# OpenPack_BATMOD_V2p0_MAN.net
KiCad netlist of a schematic drawn in Altium Designer
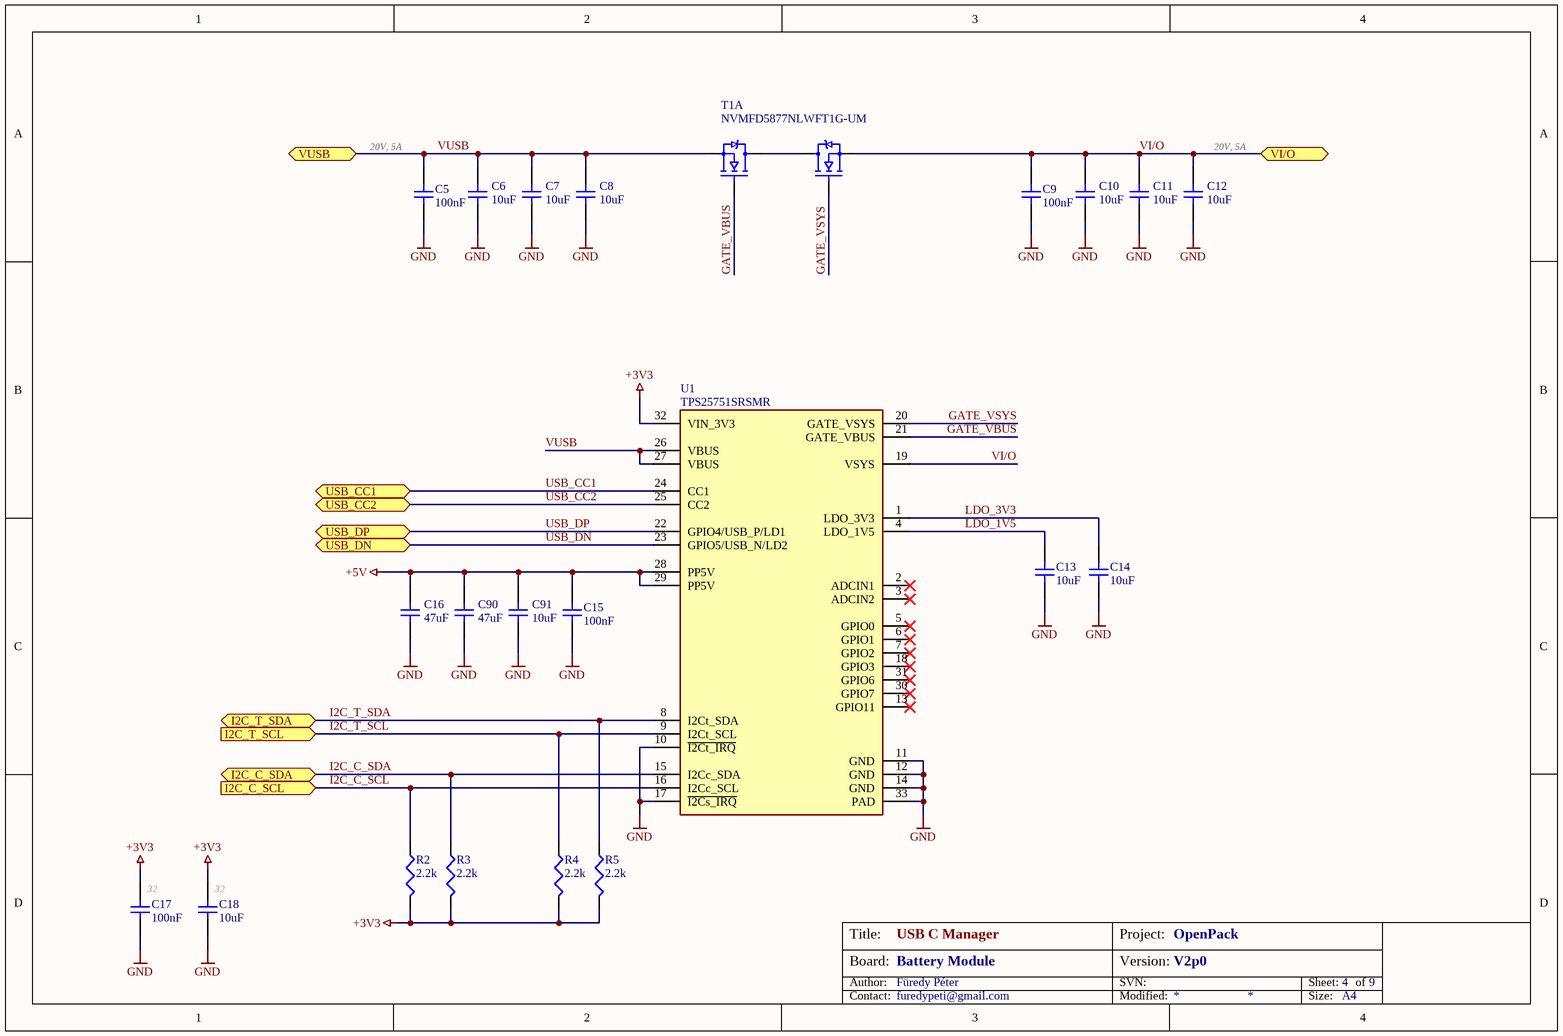
[diagram p0: OpenPack_BATMOD_V2p0_MAN.SchDoc]

(export (version "E")
  (design (tool "Eeschema 10.0.6"))
  (components
    (comp (ref "C5")
      (value "100nF")
      (footprint "CAP_0603")
      (description "MLCC capacitor")
      (libsource (lib "SCHLIB") (part "NP-CAPACITOR"))
    )
    (comp (ref "C6")
      (value "10uF")
      (footprint "CAP_1210")
      (description "UMK325BJ106KM-P")
      (fields (field (name "PART NUMBER") "810-CGA6P1X7R1N106K2"))
      (libsource (lib "SCHLIB") (part "NP-CAPACITOR"))
    )
    (comp (ref "C7")
      (value "10uF")
      (footprint "CAP_1210")
      (description "UMK325BJ106KM-P")
      (fields (field (name "PART NUMBER") "810-CGA6P1X7R1N106K2"))
      (libsource (lib "SCHLIB") (part "NP-CAPACITOR"))
    )
    (comp (ref "C8")
      (value "10uF")
      (footprint "CAP_1210")
      (description "UMK325BJ106KM-P")
      (fields (field (name "PART NUMBER") "810-CGA6P1X7R1N106K2"))
      (libsource (lib "SCHLIB") (part "NP-CAPACITOR"))
    )
    (comp (ref "C9")
      (value "100nF")
      (footprint "CAP_0603")
      (description "MLCC capacitor")
      (libsource (lib "SCHLIB") (part "NP-CAPACITOR"))
    )
    (comp (ref "C10")
      (value "10uF")
      (footprint "CAP_1210")
      (description "UMK325BJ106KM-P")
      (fields (field (name "PART NUMBER") "810-CGA6P1X7R1N106K2"))
      (libsource (lib "SCHLIB") (part "NP-CAPACITOR"))
    )
    (comp (ref "C11")
      (value "10uF")
      (footprint "CAP_1210")
      (description "UMK325BJ106KM-P")
      (fields (field (name "PART NUMBER") "810-CGA6P1X7R1N106K2"))
      (libsource (lib "SCHLIB") (part "NP-CAPACITOR"))
    )
    (comp (ref "C12")
      (value "10uF")
      (footprint "CAP_1210")
      (description "UMK325BJ106KM-P")
      (fields (field (name "PART NUMBER") "810-CGA6P1X7R1N106K2"))
      (libsource (lib "SCHLIB") (part "NP-CAPACITOR"))
    )
    (comp (ref "C13")
      (value "10uF")
      (footprint "CAP_0603")
      (description "MLCC capacitor")
      (libsource (lib "SCHLIB") (part "NP-CAPACITOR"))
    )
    (comp (ref "C14")
      (value "10uF")
      (footprint "CAP_0603")
      (description "MLCC capacitor")
      (libsource (lib "SCHLIB") (part "NP-CAPACITOR"))
    )
    (comp (ref "C15")
      (value "100nF")
      (footprint "CAP_0603")
      (description "MLCC capacitor")
      (libsource (lib "SCHLIB") (part "NP-CAPACITOR"))
    )
    (comp (ref "C16")
      (value "47uF")
      (footprint "CAP_1210")
      (description "Np-Cap")
      (fields (field (name "PART NUMBER") "80-C1210C476M4P"))
      (libsource (lib "SCHLIB") (part "NP-CAPACITOR"))
    )
    (comp (ref "C17")
      (value "100nF")
      (footprint "CAP_0603")
      (description "MLCC capacitor")
      (libsource (lib "SCHLIB") (part "NP-CAPACITOR"))
    )
    (comp (ref "C18")
      (value "10uF")
      (footprint "CAP_0603")
      (description "MLCC capacitor")
      (libsource (lib "SCHLIB") (part "NP-CAPACITOR"))
    )
    (comp (ref "C90")
      (value "47uF")
      (footprint "CAP_1210")
      (description "Np-Cap")
      (fields (field (name "PART NUMBER") "80-C1210C476M4P"))
      (libsource (lib "SCHLIB") (part "NP-CAPACITOR"))
    )
    (comp (ref "C91")
      (value "10uF")
      (footprint "CAP_1210")
      (description "UMK325BJ106KM-P")
      (fields (field (name "PART NUMBER") "810-CGA6P1X7R1N106K2"))
      (libsource (lib "SCHLIB") (part "NP-CAPACITOR"))
    )
    (comp (ref "R2")
      (value "2.2k")
      (footprint "RES-0603")
      (description "Metal Film Resistor")
      (libsource (lib "SCHLIB") (part "RESISTOR"))
    )
    (comp (ref "R3")
      (value "2.2k")
      (footprint "RES-0603")
      (description "Metal Film Resistor")
      (libsource (lib "SCHLIB") (part "RESISTOR"))
    )
    (comp (ref "R4")
      (value "2.2k")
      (footprint "RES-0603")
      (description "Metal Film Resistor")
      (libsource (lib "SCHLIB") (part "RESISTOR"))
    )
    (comp (ref "R5")
      (value "2.2k")
      (footprint "RES-0603")
      (description "Metal Film Resistor")
      (libsource (lib "SCHLIB") (part "RESISTOR"))
    )
    (comp (ref "T1")
      (value "NVMFD5877NLWFT1G-UM")
      (footprint "SO-8FL (DFN8)")
      (description "Power NMOSFET Dual, 60V, 17A, 36mΩ")
      (fields (field (name "PART NUMBER") "863-FD5877NLWFT1G-UM"))
      (libsource (lib "SCHLIB") (part "NVMFD5877NLWFT1G-UM"))
    )
    (comp (ref "U1")
      (value "TPS25751SRSMR")
      (footprint "QFN32 - 0.4mm")
      (description "USB Interface IC USB Type-C and USB P ower Delivery (PD)")
      (fields (field (name "PART NUMBER") "595-TPS25751SRSMR"))
      (libsource (lib "SCHLIB") (part "TPS25751SRSMR"))
    )
  )
  (nets
    (net (code "1") (name "+3V3") (class "Default")
      (node (ref "C17") (pin "2") (pinfunction "2_2") (pintype "passive"))
      (node (ref "C18") (pin "2") (pinfunction "2_2") (pintype "passive"))
      (node (ref "R2") (pin "2") (pintype "passive"))
      (node (ref "R3") (pin "2") (pintype "passive"))
      (node (ref "R4") (pin "2") (pintype "passive"))
      (node (ref "R5") (pin "2") (pintype "passive"))
      (node (ref "U1") (pin "32") (pinfunction "VIN_3V3_32") (pintype "passive"))
    )
    (net (code "2") (name "+5V") (class "Default")
      (node (ref "C15") (pin "2") (pinfunction "2_2") (pintype "passive"))
      (node (ref "C16") (pin "2") (pinfunction "2_2") (pintype "passive"))
      (node (ref "C90") (pin "2") (pinfunction "2_2") (pintype "passive"))
      (node (ref "C91") (pin "2") (pinfunction "2_2") (pintype "passive"))
      (node (ref "U1") (pin "28") (pinfunction "PP5V_28") (pintype "passive"))
      (node (ref "U1") (pin "29") (pinfunction "PP5V_29") (pintype "passive"))
    )
    (net (code "3") (name "/GATE_VBUS") (class "Default")
      (node (ref "T1") (pin "4") (pinfunction "4_4") (pintype "passive"))
      (node (ref "U1") (pin "21") (pinfunction "GATE_VBUS_21") (pintype "passive"))
    )
    (net (code "4") (name "/GATE_VSYS") (class "Default")
      (node (ref "T1") (pin "2") (pinfunction "2_2") (pintype "passive"))
      (node (ref "U1") (pin "20") (pinfunction "GATE_VSYS_20") (pintype "passive"))
    )
    (net (code "5") (name "/I2C_C_SCL") (class "Default")
      (node (ref "R2") (pin "1") (pintype "passive"))
      (node (ref "U1") (pin "16") (pinfunction "I2Cc_SCL_16") (pintype "passive"))
    )
    (net (code "6") (name "/I2C_C_SDA") (class "Default")
      (node (ref "R3") (pin "1") (pintype "passive"))
      (node (ref "U1") (pin "15") (pinfunction "I2Cc_SDA_15") (pintype "passive"))
    )
    (net (code "7") (name "/I2C_T_SCL") (class "Default")
      (node (ref "R4") (pin "1") (pintype "passive"))
      (node (ref "U1") (pin "9") (pinfunction "I2Ct_SCL_9") (pintype "passive"))
    )
    (net (code "8") (name "/I2C_T_SDA") (class "Default")
      (node (ref "R5") (pin "1") (pintype "passive"))
      (node (ref "U1") (pin "8") (pinfunction "I2Ct_SDA_8") (pintype "passive"))
    )
    (net (code "9") (name "/LDO_1V5") (class "Default")
      (node (ref "C13") (pin "2") (pinfunction "2_2") (pintype "passive"))
      (node (ref "U1") (pin "4") (pinfunction "LDO_1V5_4") (pintype "passive"))
    )
    (net (code "10") (name "/LDO_3V3") (class "Default")
      (node (ref "C14") (pin "2") (pinfunction "2_2") (pintype "passive"))
      (node (ref "U1") (pin "1") (pinfunction "LDO_3V3_1") (pintype "passive"))
    )
    (net (code "11") (name "/USB_CC1") (class "Default")
      (node (ref "U1") (pin "24") (pinfunction "CC1_24") (pintype "passive"))
    )
    (net (code "12") (name "/USB_CC2") (class "Default")
      (node (ref "U1") (pin "25") (pinfunction "CC2_25") (pintype "passive"))
    )
    (net (code "13") (name "/USB_DN") (class "Default")
      (node (ref "U1") (pin "23") (pinfunction "GPIO5/USB_N/LD2_23") (pintype "passive"))
    )
    (net (code "14") (name "/USB_DP") (class "Default")
      (node (ref "U1") (pin "22") (pinfunction "GPIO4/USB_P/LD1_22") (pintype "passive"))
    )
    (net (code "15") (name "/VI{slash}O") (class "Default")
      (node (ref "C10") (pin "2") (pinfunction "2_2") (pintype "passive"))
      (node (ref "C11") (pin "2") (pinfunction "2_2") (pintype "passive"))
      (node (ref "C12") (pin "2") (pinfunction "2_2") (pintype "passive"))
      (node (ref "C9") (pin "2") (pinfunction "2_2") (pintype "passive"))
      (node (ref "T1") (pin "1") (pinfunction "1_1") (pintype "passive"))
      (node (ref "U1") (pin "19") (pinfunction "VSYS_19") (pintype "passive"))
    )
    (net (code "16") (name "/VUSB") (class "Default")
      (node (ref "C5") (pin "2") (pinfunction "2_2") (pintype "passive"))
      (node (ref "C6") (pin "2") (pinfunction "2_2") (pintype "passive"))
      (node (ref "C7") (pin "2") (pinfunction "2_2") (pintype "passive"))
      (node (ref "C8") (pin "2") (pinfunction "2_2") (pintype "passive"))
      (node (ref "T1") (pin "3") (pinfunction "3_3") (pintype "passive"))
      (node (ref "U1") (pin "26") (pinfunction "VBUS_26") (pintype "passive"))
      (node (ref "U1") (pin "27") (pinfunction "VBUS_27") (pintype "passive"))
    )
    (net (code "17") (name "GND") (class "Default")
      (node (ref "C10") (pin "1") (pinfunction "1_1") (pintype "passive"))
      (node (ref "C11") (pin "1") (pinfunction "1_1") (pintype "passive"))
      (node (ref "C12") (pin "1") (pinfunction "1_1") (pintype "passive"))
      (node (ref "C13") (pin "1") (pinfunction "1_1") (pintype "passive"))
      (node (ref "C14") (pin "1") (pinfunction "1_1") (pintype "passive"))
      (node (ref "C15") (pin "1") (pinfunction "1_1") (pintype "passive"))
      (node (ref "C16") (pin "1") (pinfunction "1_1") (pintype "passive"))
      (node (ref "C17") (pin "1") (pinfunction "1_1") (pintype "passive"))
      (node (ref "C18") (pin "1") (pinfunction "1_1") (pintype "passive"))
      (node (ref "C5") (pin "1") (pinfunction "1_1") (pintype "passive"))
      (node (ref "C6") (pin "1") (pinfunction "1_1") (pintype "passive"))
      (node (ref "C7") (pin "1") (pinfunction "1_1") (pintype "passive"))
      (node (ref "C8") (pin "1") (pinfunction "1_1") (pintype "passive"))
      (node (ref "C9") (pin "1") (pinfunction "1_1") (pintype "passive"))
      (node (ref "C90") (pin "1") (pinfunction "1_1") (pintype "passive"))
      (node (ref "C91") (pin "1") (pinfunction "1_1") (pintype "passive"))
      (node (ref "U1") (pin "10") (pinfunction "~{I2Ct_IRQ}_10") (pintype "passive"))
      (node (ref "U1") (pin "11") (pinfunction "GND_11") (pintype "passive"))
      (node (ref "U1") (pin "12") (pinfunction "GND_12") (pintype "passive"))
      (node (ref "U1") (pin "14") (pinfunction "GND_14") (pintype "passive"))
      (node (ref "U1") (pin "17") (pinfunction "~{I2Cs_IRQ}_17") (pintype "passive"))
      (node (ref "U1") (pin "33") (pinfunction "PAD_33") (pintype "passive"))
    )
    (net (code "18") (name "Net-(T1-Pad10)") (class "Default")
      (node (ref "T1") (pin "10") (pinfunction "10_10") (pintype "passive"))
      (node (ref "T1") (pin "9") (pinfunction "9_9") (pintype "passive"))
    )
    (net (code "19") (name "unconnected-(U1-ADCIN1-Pad2)") (class "Default")
      (node (ref "U1") (pin "2") (pinfunction "ADCIN1_2") (pintype "passive+no_connect"))
    )
    (net (code "20") (name "unconnected-(U1-ADCIN2-Pad3)") (class "Default")
      (node (ref "U1") (pin "3") (pinfunction "ADCIN2_3") (pintype "passive+no_connect"))
    )
    (net (code "21") (name "unconnected-(U1-GPIO0-Pad5)") (class "Default")
      (node (ref "U1") (pin "5") (pinfunction "GPIO0_5") (pintype "passive+no_connect"))
    )
    (net (code "22") (name "unconnected-(U1-GPIO1-Pad6)") (class "Default")
      (node (ref "U1") (pin "6") (pinfunction "GPIO1_6") (pintype "passive+no_connect"))
    )
    (net (code "23") (name "unconnected-(U1-GPIO2-Pad7)") (class "Default")
      (node (ref "U1") (pin "7") (pinfunction "GPIO2_7") (pintype "passive+no_connect"))
    )
    (net (code "24") (name "unconnected-(U1-GPIO3-Pad18)") (class "Default")
      (node (ref "U1") (pin "18") (pinfunction "GPIO3_18") (pintype "passive+no_connect"))
    )
    (net (code "25") (name "unconnected-(U1-GPIO6-Pad31)") (class "Default")
      (node (ref "U1") (pin "31") (pinfunction "GPIO6_31") (pintype "passive+no_connect"))
    )
    (net (code "26") (name "unconnected-(U1-GPIO7-Pad30)") (class "Default")
      (node (ref "U1") (pin "30") (pinfunction "GPIO7_30") (pintype "passive+no_connect"))
    )
    (net (code "27") (name "unconnected-(U1-GPIO11-Pad13)") (class "Default")
      (node (ref "U1") (pin "13") (pinfunction "GPIO11_13") (pintype "passive+no_connect"))
    )
  )
)
